# SPI_IFC.net
KiCad netlist of a schematic drawn in Altium Designer
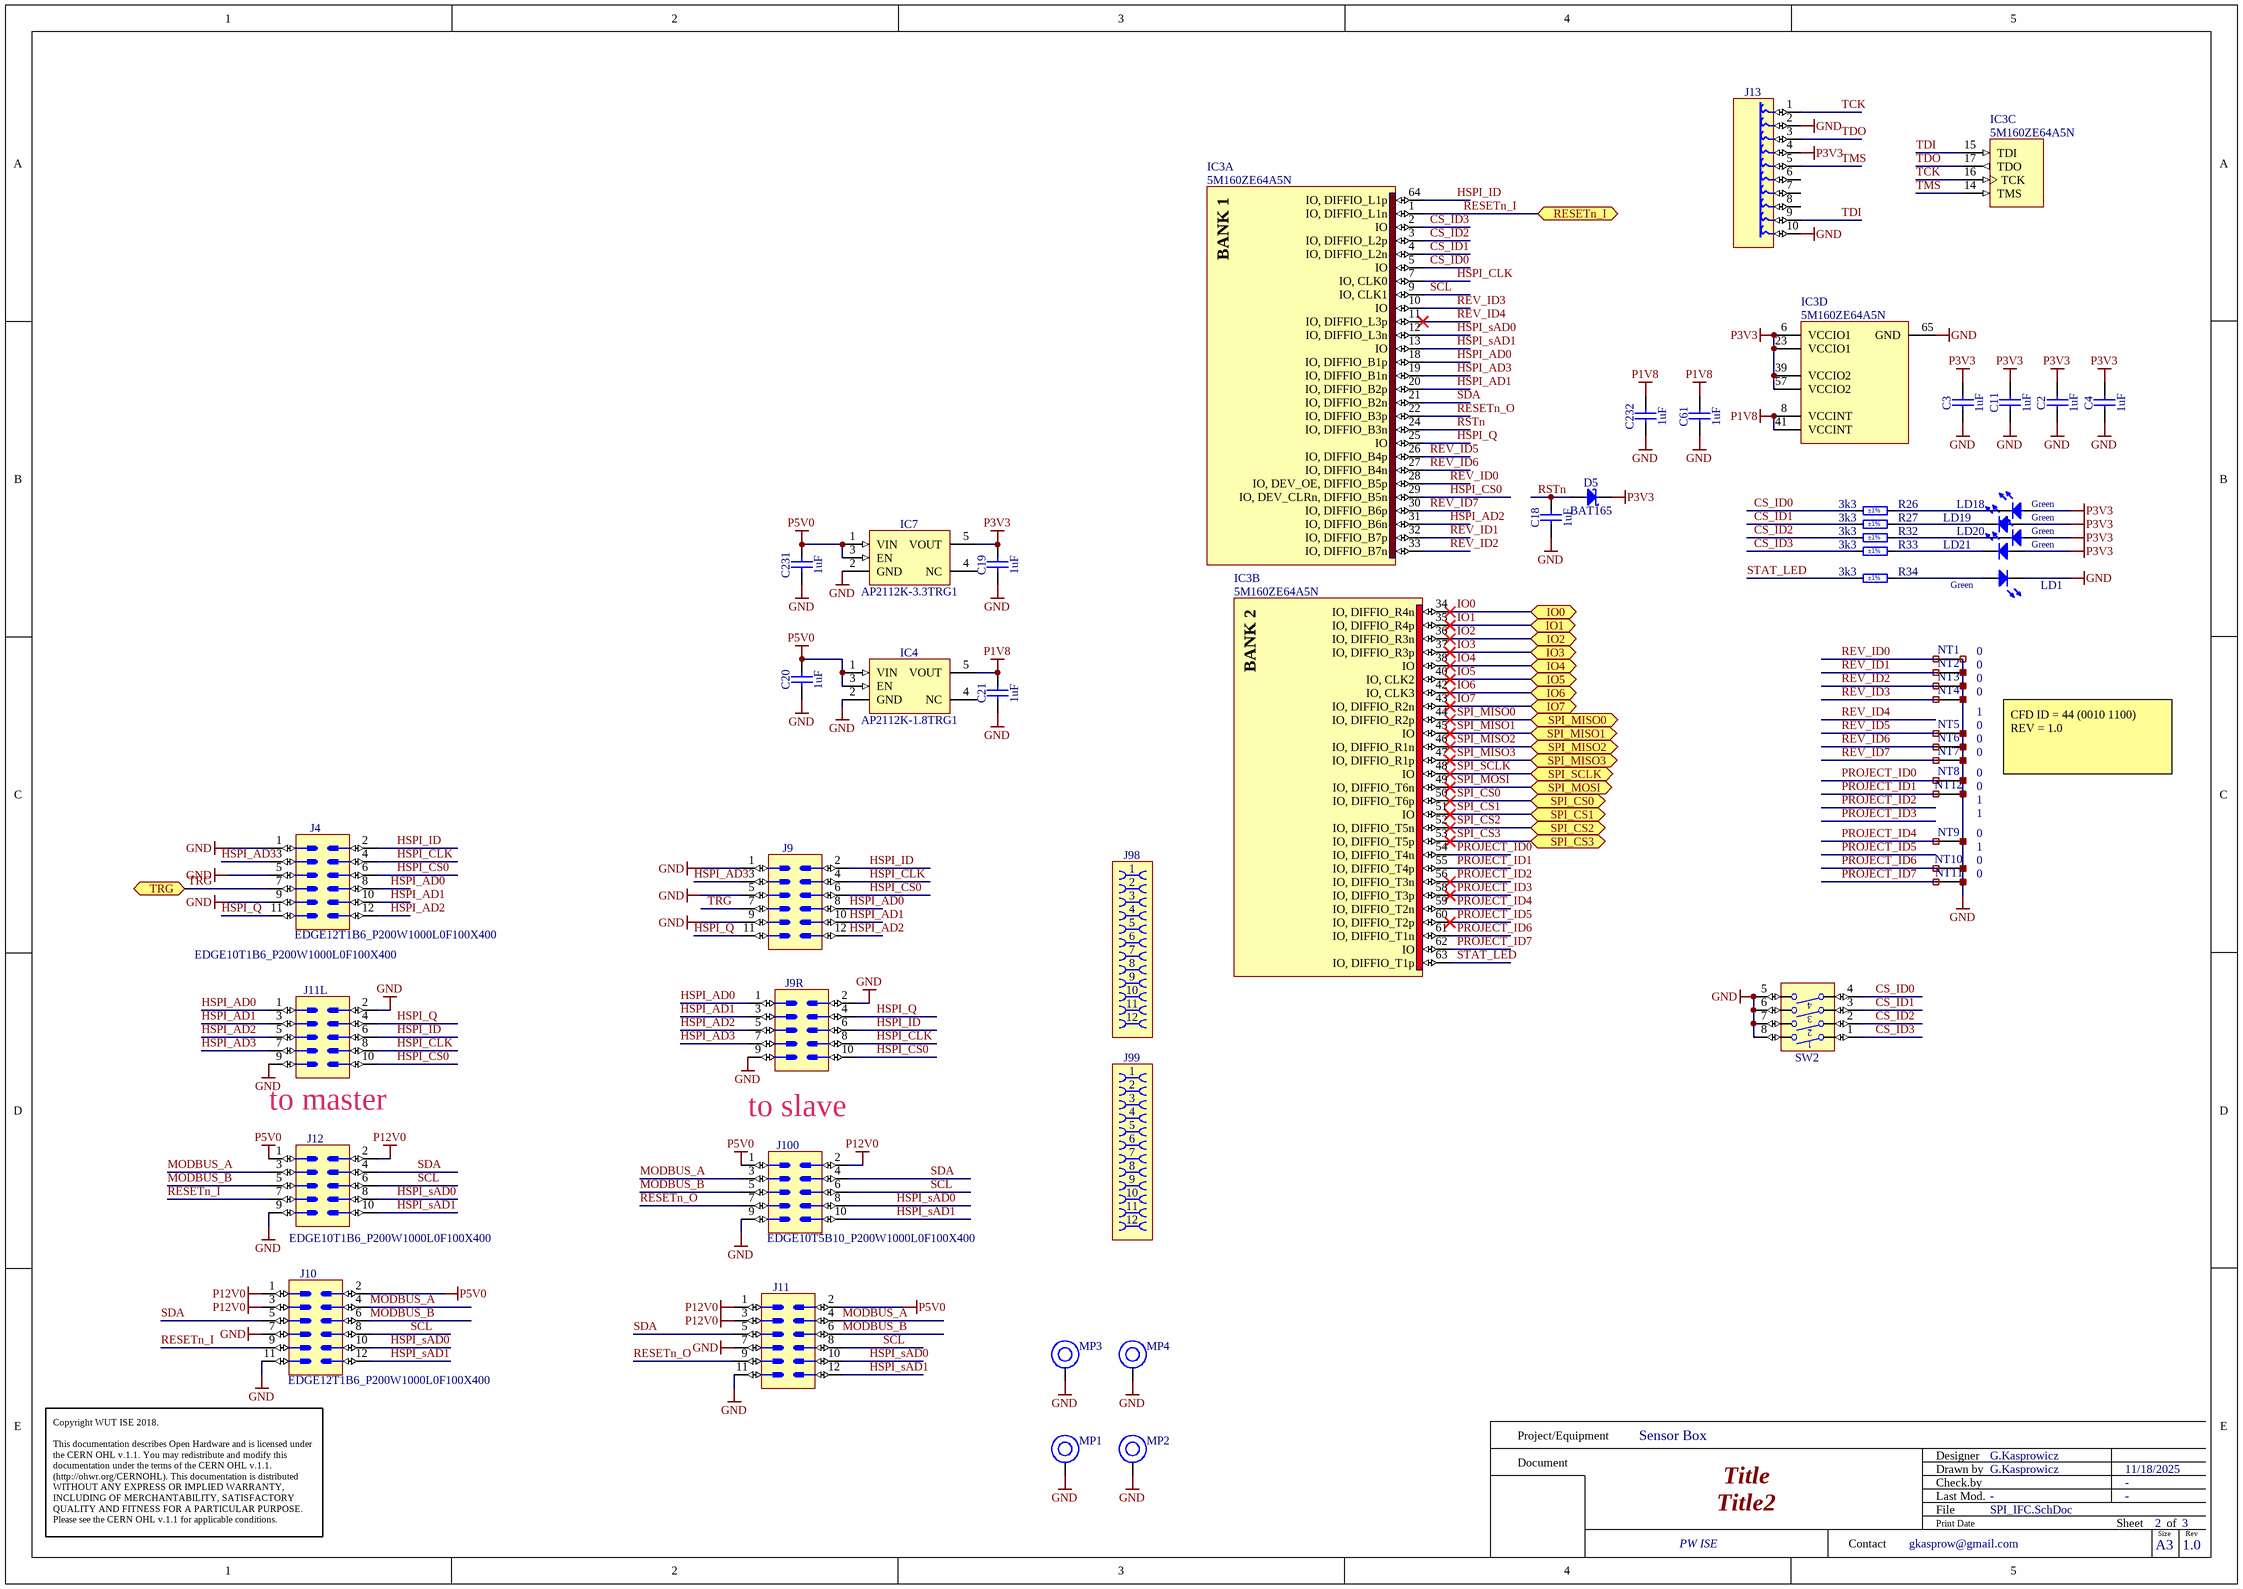
[diagram p0: SPI_IFC.SchDoc]

(export (version "E")
  (design (tool "Eeschema 10.0.6"))
  (components
    (comp (ref "C2")
      (value "1uF")
      (footprint "CAPC1005X55N")
      (description "Non-polarised capacitor")
      (fields
        (field (name "PART NUMBER") "CC0402_1UF_16V_10%_X5R")
        (field (name "VOLTAGE") "16V")
        (field (name "AUTHOR") "CERN DEM JLC")
      )
      (libsource (lib "Capacitors") (part "Capacitor - non polarized"))
    )
    (comp (ref "C3")
      (value "1uF")
      (footprint "CAPC1005X55N")
      (description "Non-polarised capacitor")
      (fields
        (field (name "PART NUMBER") "CC0402_1UF_16V_10%_X5R")
        (field (name "VOLTAGE") "16V")
        (field (name "AUTHOR") "CERN DEM JLC")
      )
      (libsource (lib "Capacitors") (part "Capacitor - non polarized"))
    )
    (comp (ref "C4")
      (value "1uF")
      (footprint "CAPC1005X55N")
      (description "Non-polarised capacitor")
      (fields
        (field (name "PART NUMBER") "CC0402_1UF_16V_10%_X5R")
        (field (name "VOLTAGE") "16V")
        (field (name "AUTHOR") "CERN DEM JLC")
      )
      (libsource (lib "Capacitors") (part "Capacitor - non polarized"))
    )
    (comp (ref "C11")
      (value "1uF")
      (footprint "CAPC1005X55N")
      (description "Non-polarised capacitor")
      (fields
        (field (name "PART NUMBER") "CC0402_1UF_16V_10%_X5R")
        (field (name "VOLTAGE") "16V")
        (field (name "AUTHOR") "CERN DEM JLC")
      )
      (libsource (lib "Capacitors") (part "Capacitor - non polarized"))
    )
    (comp (ref "C18")
      (value "1uF")
      (footprint "CAPC1005X55N")
      (description "Non-polarised capacitor")
      (fields
        (field (name "PART NUMBER") "CC0402_1UF_16V_10%_X5R")
        (field (name "VOLTAGE") "16V")
        (field (name "AUTHOR") "CERN DEM JLC")
      )
      (libsource (lib "Capacitors") (part "Capacitor - non polarized"))
    )
    (comp (ref "C19")
      (value "1uF")
      (footprint "CAPC1005X55N")
      (description "Non-polarised capacitor")
      (fields
        (field (name "PART NUMBER") "CC0402_1UF_16V_10%_X5R")
        (field (name "VOLTAGE") "16V")
        (field (name "AUTHOR") "CERN DEM JLC")
      )
      (libsource (lib "Capacitors") (part "Capacitor - non polarized"))
    )
    (comp (ref "C20")
      (value "1uF")
      (footprint "CAPC1005X55N")
      (description "Non-polarised capacitor")
      (fields
        (field (name "PART NUMBER") "CC0402_1UF_16V_10%_X5R")
        (field (name "VOLTAGE") "16V")
        (field (name "AUTHOR") "CERN DEM JLC")
      )
      (libsource (lib "Capacitors") (part "Capacitor - non polarized"))
    )
    (comp (ref "C21")
      (value "1uF")
      (footprint "CAPC1005X55N")
      (description "Non-polarised capacitor")
      (fields
        (field (name "PART NUMBER") "CC0402_1UF_16V_10%_X5R")
        (field (name "VOLTAGE") "16V")
        (field (name "AUTHOR") "CERN DEM JLC")
      )
      (libsource (lib "Capacitors") (part "Capacitor - non polarized"))
    )
    (comp (ref "C61")
      (value "1uF")
      (footprint "CAPC1005X55N")
      (description "Non-polarised capacitor")
      (fields
        (field (name "PART NUMBER") "CC0402_1UF_16V_10%_X5R")
        (field (name "VOLTAGE") "16V")
        (field (name "AUTHOR") "CERN DEM JLC")
      )
      (libsource (lib "Capacitors") (part "Capacitor - non polarized"))
    )
    (comp (ref "C231")
      (value "1uF")
      (footprint "CAPC1005X55N")
      (description "Non-polarised capacitor")
      (fields
        (field (name "PART NUMBER") "CC0402_1UF_16V_10%_X5R")
        (field (name "VOLTAGE") "16V")
        (field (name "AUTHOR") "CERN DEM JLC")
      )
      (libsource (lib "Capacitors") (part "Capacitor - non polarized"))
    )
    (comp (ref "C232")
      (value "1uF")
      (footprint "CAPC1005X55N")
      (description "Non-polarised capacitor")
      (fields
        (field (name "PART NUMBER") "CC0402_1UF_16V_10%_X5R")
        (field (name "VOLTAGE") "16V")
        (field (name "AUTHOR") "CERN DEM JLC")
      )
      (libsource (lib "Capacitors") (part "Capacitor - non polarized"))
    )
    (comp (ref "D5")
      (value "BAT165")
      (footprint "SOD2512X110N")
      (description "Schottky Diode")
      (fields
        (field (name "VOLTAGE") "40V")
        (field (name "POWER") "750mA")
        (field (name "AUTHOR") "CERN DEM JLC")
      )
      (libsource (lib "ICs And Semiconductors") (part "Diode Schottky"))
    )
    (comp (ref "IC3")
      (value "5M160ZE64A5N")
      (footprint "QFP40P900X900X120-65N-S550")
      (fields (field (name "MANUFACTURER") "ALTERA") (field (name "AUTHOR") "CERN DEM JLC"))
      (libsource (lib "ICs And Semiconductors") (part "5M160ZE64A5N"))
    )
    (comp (ref "IC4")
      (value "AP2112K-1.8TRG1")
      (footprint "SOT95P285X140-5N")
      (description "600mA CMOS Low Dropout Linear Regulator with Enable")
      (fields
        (field (name "MANUFACTURER") "DIODES INCORPORATED")
        (field (name "MANUFACTURER PART NUMBER") "AP2112K-1.8")
        (field (name "AUTHOR") "CERN DEM JLC")
      )
      (libsource (lib "ICs And Semiconductors") (part "AP2112K"))
    )
    (comp (ref "IC7")
      (value "AP2112K-3.3TRG1")
      (footprint "SOT95P285X140-5N")
      (description "600mA CMOS Low Dropout Linear Regulator with Enable")
      (fields
        (field (name "MANUFACTURER") "DIODES INCORPORATED")
        (field (name "MANUFACTURER PART NUMBER") "AP2112K-3.3")
        (field (name "AUTHOR") "CERN DEM MR")
      )
      (libsource (lib "ICs And Semiconductors") (part "AP2112K"))
    )
    (comp (ref "J4")
      (value "~")
      (footprint "EDGE12T1B6_P200W1000L0F100X400")
      (description "PCB Edge Connector 12 (2x6)")
      (fields
        (field (name "PART NUMBER") "EDGE10T1B6_P200W1000L0F100X400")
        (field (name "AUTHOR") "CERN DEM MR")
      )
      (libsource (lib "Connectors") (part "PCB Edge Connector 12 (2x6)"))
    )
    (comp (ref "J9")
      (value "~")
      (footprint "EDGE12T5B10_P200W1000L0F100X400")
      (description "PCB Edge Connector 12 (2x6)")
      (fields (field (name "PART NUMBER") "EDGE12T5B10_P200W1000L0F100X400") (field (name "AUTHOR") "GK"))
      (libsource (lib "Connectors") (part "PCB Edge Connector 12 (2x6) R"))
    )
    (comp (ref "J9R")
      (value "~")
      (footprint "EDGE10T5B10_P200W1000L0F100X400")
      (description "PCB Edge Connector 10 (2x5)")
      (fields
        (field (name "PART NUMBER") "EDGE10T5B10_P200W1000L0F100X400")
        (field (name "AUTHOR") "CERN DEM MR")
      )
      (libsource (lib "Connectors") (part "PCB Edge Connector 10 (2x5)"))
    )
    (comp (ref "J10")
      (value "~")
      (footprint "EDGE12T1B6_P200W1000L0F100X400")
      (description "PCB Edge Connector 12 (2x6)")
      (fields
        (field (name "PART NUMBER") "EDGE10T1B6_P200W1000L0F100X400")
        (field (name "AUTHOR") "CERN DEM MR")
      )
      (libsource (lib "Connectors") (part "PCB Edge Connector 12 (2x6)"))
    )
    (comp (ref "J11")
      (value "~")
      (footprint "EDGE12T5B10_P200W1000L0F100X400")
      (description "PCB Edge Connector 12 (2x6)")
      (fields (field (name "PART NUMBER") "EDGE12T5B10_P200W1000L0F100X400") (field (name "AUTHOR") "GK"))
      (libsource (lib "Connectors") (part "PCB Edge Connector 12 (2x6) R"))
    )
    (comp (ref "J11L")
      (value "~")
      (footprint "EDGE10T1B6_P200W1000L0F100X400")
      (description "PCB Edge Connector 10 (2x5)")
      (fields
        (field (name "PART NUMBER") "EDGE10T1B6_P200W1000L0F100X400")
        (field (name "AUTHOR") "CERN DEM MR")
      )
      (libsource (lib "Connectors") (part "PCB Edge Connector 10 (2x5)"))
    )
    (comp (ref "J12")
      (value "~")
      (footprint "EDGE10T1B6_P200W1000L0F100X400")
      (description "PCB Edge Connector 10 (2x5)")
      (fields
        (field (name "PART NUMBER") "EDGE10T1B6_P200W1000L0F100X400")
        (field (name "AUTHOR") "CERN DEM MR")
      )
      (libsource (lib "Connectors") (part "PCB Edge Connector 10 (2x5)"))
    )
    (comp (ref "J13")
      (value "TC2050-IDC")
      (footprint "TC2050-IDC")
      (description "TC2030-MCP and TC2050-IDC Pad Contact")
      (fields (field (name "AUTHOR") "CERN DEM HF"))
      (libsource (lib "Eletro-mechanical") (part "TC2050-IDC"))
    )
    (comp (ref "J98")
      (value "~")
      (footprint "AVX_009159012761916")
      (description "Open Ended Card Edge Connector, 9159 Series")
      (fields
        (field (name "PART NUMBER") "AVX_0009159012761916")
        (field (name "MANUFACTURER") "AVX")
        (field (name "AUTHOR") "GK")
      )
      (libsource (lib "Connectors") (part "AVX_009159012761916"))
    )
    (comp (ref "J99")
      (value "~")
      (footprint "AVX_009159012761916")
      (description "Open Ended Card Edge Connector, 9159 Series")
      (fields
        (field (name "PART NUMBER") "AVX_0009159012761916")
        (field (name "MANUFACTURER") "AVX")
        (field (name "AUTHOR") "GK")
      )
      (libsource (lib "Connectors") (part "AVX_009159012761916"))
    )
    (comp (ref "J100")
      (value "~")
      (footprint "EDGE10T5B10_P200W1000L0F100X400")
      (description "PCB Edge Connector 10 (2x5)")
      (fields
        (field (name "PART NUMBER") "EDGE10T5B10_P200W1000L0F100X400")
        (field (name "AUTHOR") "CERN DEM MR")
      )
      (libsource (lib "Connectors") (part "PCB Edge Connector 10 (2x5)"))
    )
    (comp (ref "LD1")
      (value "Green")
      (footprint "LED_KINGBRIGHT_KP-1608CGCK")
      (description "LED Green 1C 2A")
      (fields
        (field (name "PART NUMBER") "LED_KINGBRIGHT_KP-1608CGCK")
        (field (name "MANUFACTURER") "KINGBRIGHT")
        (field (name "AUTHOR") "CERN DEM HF")
      )
      (libsource (lib "ICs And Semiconductors") (part "LED Green 1C 2A"))
    )
    (comp (ref "LD18")
      (value "Green")
      (footprint "LED_KINGBRIGHT_KP-1608CGCK")
      (description "LED Green 1C 2A")
      (fields
        (field (name "PART NUMBER") "LED_KINGBRIGHT_KP-1608CGCK")
        (field (name "MANUFACTURER") "KINGBRIGHT")
        (field (name "AUTHOR") "CERN DEM HF")
      )
      (libsource (lib "ICs And Semiconductors") (part "LED Green 1C 2A"))
    )
    (comp (ref "LD19")
      (value "Green")
      (footprint "LED_KINGBRIGHT_KP-1608CGCK")
      (description "LED Green 1C 2A")
      (fields
        (field (name "PART NUMBER") "LED_KINGBRIGHT_KP-1608CGCK")
        (field (name "MANUFACTURER") "KINGBRIGHT")
        (field (name "AUTHOR") "CERN DEM HF")
      )
      (libsource (lib "ICs And Semiconductors") (part "LED Green 1C 2A"))
    )
    (comp (ref "LD20")
      (value "Green")
      (footprint "LED_KINGBRIGHT_KP-1608CGCK")
      (description "LED Green 1C 2A")
      (fields
        (field (name "PART NUMBER") "LED_KINGBRIGHT_KP-1608CGCK")
        (field (name "MANUFACTURER") "KINGBRIGHT")
        (field (name "AUTHOR") "CERN DEM HF")
      )
      (libsource (lib "ICs And Semiconductors") (part "LED Green 1C 2A"))
    )
    (comp (ref "LD21")
      (value "Green")
      (footprint "LED_KINGBRIGHT_KP-1608CGCK")
      (description "LED Green 1C 2A")
      (fields
        (field (name "PART NUMBER") "LED_KINGBRIGHT_KP-1608CGCK")
        (field (name "MANUFACTURER") "KINGBRIGHT")
        (field (name "AUTHOR") "CERN DEM HF")
      )
      (libsource (lib "ICs And Semiconductors") (part "LED Green 1C 2A"))
    )
    (comp (ref "MP1")
      (value "M1.6 x 3mm")
      (footprint "97730306330")
      (description "WA-SMSI SMT Steel Spacer with internal Thread Bottom closed, OD 3.3mm, M1.6 x 3mm")
      (fields
        (field (name "MANUFACTURER PART NUMBER") "97730306330R")
        (field (name "MANUFACTURER") "Wurth Elektronik")
      )
      (libsource (lib "Altium_WA-SMSI (rev22a)") (part "97730306330R"))
    )
    (comp (ref "MP2")
      (value "M1.6 x 3mm")
      (footprint "97730306330")
      (description "WA-SMSI SMT Steel Spacer with internal Thread Bottom closed, OD 3.3mm, M1.6 x 3mm")
      (fields
        (field (name "MANUFACTURER PART NUMBER") "97730306330R")
        (field (name "MANUFACTURER") "Wurth Elektronik")
      )
      (libsource (lib "Altium_WA-SMSI (rev22a)") (part "97730306330R"))
    )
    (comp (ref "MP3")
      (value "M1.6 x 3mm")
      (footprint "97730306330")
      (description "WA-SMSI SMT Steel Spacer with internal Thread Bottom closed, OD 3.3mm, M1.6 x 3mm")
      (fields
        (field (name "MANUFACTURER PART NUMBER") "97730306330R")
        (field (name "MANUFACTURER") "Wurth Elektronik")
      )
      (libsource (lib "Altium_WA-SMSI (rev22a)") (part "97730306330R"))
    )
    (comp (ref "MP4")
      (value "M1.6 x 3mm")
      (footprint "97730306330")
      (description "WA-SMSI SMT Steel Spacer with internal Thread Bottom closed, OD 3.3mm, M1.6 x 3mm")
      (fields
        (field (name "MANUFACTURER PART NUMBER") "97730306330R")
        (field (name "MANUFACTURER") "Wurth Elektronik")
      )
      (libsource (lib "Altium_WA-SMSI (rev22a)") (part "97730306330R"))
    )
    (comp (ref "NT1")
      (value "Net Tie")
      (footprint "Net Tie 3")
      (fields (field (name "PART NUMBER") "Net Tie 3") (field (name "AUTHOR") "CERN DEM HF"))
      (libsource (lib "Eletro-mechanical") (part "Net Tie_a"))
    )
    (comp (ref "NT2")
      (value "Net Tie")
      (footprint "Net Tie 3")
      (fields (field (name "PART NUMBER") "Net Tie 3") (field (name "AUTHOR") "CERN DEM HF"))
      (libsource (lib "Eletro-mechanical") (part "Net Tie_a"))
    )
    (comp (ref "NT3")
      (value "Net Tie")
      (footprint "Net Tie 3")
      (fields (field (name "PART NUMBER") "Net Tie 3") (field (name "AUTHOR") "CERN DEM HF"))
      (libsource (lib "Eletro-mechanical") (part "Net Tie_a"))
    )
    (comp (ref "NT4")
      (value "Net Tie")
      (footprint "Net Tie 3")
      (fields (field (name "PART NUMBER") "Net Tie 3") (field (name "AUTHOR") "CERN DEM HF"))
      (libsource (lib "Eletro-mechanical") (part "Net Tie_a"))
    )
    (comp (ref "NT5")
      (value "Net Tie")
      (footprint "Net Tie 3")
      (fields (field (name "PART NUMBER") "Net Tie 3") (field (name "AUTHOR") "CERN DEM HF"))
      (libsource (lib "Eletro-mechanical") (part "Net Tie_a"))
    )
    (comp (ref "NT6")
      (value "Net Tie")
      (footprint "Net Tie 3")
      (fields (field (name "PART NUMBER") "Net Tie 3") (field (name "AUTHOR") "CERN DEM HF"))
      (libsource (lib "Eletro-mechanical") (part "Net Tie_a"))
    )
    (comp (ref "NT7")
      (value "Net Tie")
      (footprint "Net Tie 3")
      (fields (field (name "PART NUMBER") "Net Tie 3") (field (name "AUTHOR") "CERN DEM HF"))
      (libsource (lib "Eletro-mechanical") (part "Net Tie_a"))
    )
    (comp (ref "NT8")
      (value "Net Tie")
      (footprint "Net Tie 3")
      (fields (field (name "PART NUMBER") "Net Tie 3") (field (name "AUTHOR") "CERN DEM HF"))
      (libsource (lib "Eletro-mechanical") (part "Net Tie_a"))
    )
    (comp (ref "NT9")
      (value "Net Tie")
      (footprint "Net Tie 3")
      (fields (field (name "PART NUMBER") "Net Tie 3") (field (name "AUTHOR") "CERN DEM HF"))
      (libsource (lib "Eletro-mechanical") (part "Net Tie_a"))
    )
    (comp (ref "NT10")
      (value "Net Tie")
      (footprint "Net Tie 3")
      (fields (field (name "PART NUMBER") "Net Tie 3") (field (name "AUTHOR") "CERN DEM HF"))
      (libsource (lib "Eletro-mechanical") (part "Net Tie_a"))
    )
    (comp (ref "NT11")
      (value "Net Tie")
      (footprint "Net Tie 3")
      (fields (field (name "PART NUMBER") "Net Tie 3") (field (name "AUTHOR") "CERN DEM HF"))
      (libsource (lib "Eletro-mechanical") (part "Net Tie_a"))
    )
    (comp (ref "NT12")
      (value "Net Tie")
      (footprint "Net Tie 3")
      (fields (field (name "PART NUMBER") "Net Tie 3") (field (name "AUTHOR") "CERN DEM HF"))
      (libsource (lib "Eletro-mechanical") (part "Net Tie_a"))
    )
    (comp (ref "R26")
      (value "3k3")
      (footprint "RESC1005X40N")
      (description "Resistor - 1%")
      (fields
        (field (name "TOLERANCE") "±1%")
        (field (name "PART NUMBER") "R0402_3K3_1%_0.0625W_100PPM")
        (field (name "POWER") "0.0625W")
        (field (name "AUTHOR") "CERN DEM JLC")
      )
      (libsource (lib "Resistors") (part "Resistor - 1%"))
    )
    (comp (ref "R27")
      (value "3k3")
      (footprint "RESC1005X40N")
      (description "Resistor - 1%")
      (fields
        (field (name "TOLERANCE") "±1%")
        (field (name "PART NUMBER") "R0402_3K3_1%_0.0625W_100PPM")
        (field (name "POWER") "0.0625W")
        (field (name "AUTHOR") "CERN DEM JLC")
      )
      (libsource (lib "Resistors") (part "Resistor - 1%"))
    )
    (comp (ref "R32")
      (value "3k3")
      (footprint "RESC1005X40N")
      (description "Resistor - 1%")
      (fields
        (field (name "TOLERANCE") "±1%")
        (field (name "PART NUMBER") "R0402_3K3_1%_0.0625W_100PPM")
        (field (name "POWER") "0.0625W")
        (field (name "AUTHOR") "CERN DEM JLC")
      )
      (libsource (lib "Resistors") (part "Resistor - 1%"))
    )
    (comp (ref "R33")
      (value "3k3")
      (footprint "RESC1005X40N")
      (description "Resistor - 1%")
      (fields
        (field (name "TOLERANCE") "±1%")
        (field (name "PART NUMBER") "R0402_3K3_1%_0.0625W_100PPM")
        (field (name "POWER") "0.0625W")
        (field (name "AUTHOR") "CERN DEM JLC")
      )
      (libsource (lib "Resistors") (part "Resistor - 1%"))
    )
    (comp (ref "R34")
      (value "3k3")
      (footprint "RESC1005X40N")
      (description "Resistor - 1%")
      (fields
        (field (name "TOLERANCE") "±1%")
        (field (name "PART NUMBER") "R0402_3K3_1%_0.0625W_100PPM")
        (field (name "POWER") "0.0625W")
        (field (name "AUTHOR") "CERN DEM JLC")
      )
      (libsource (lib "Resistors") (part "Resistor - 1%"))
    )
    (comp (ref "SW2")
      (value "Switch")
      (footprint "SW_OMRON_A6H-4102")
      (description "4 Ways SPST DIP Switch")
      (fields
        (field (name "PART NUMBER") "SW_OMRON_A6H-4102")
        (field (name "MANUFACTURER") "OMRON")
        (field (name "AUTHOR") "CERN DEM JLC")
      )
      (libsource (lib "Eletro-mechanical") (part "SW 4x SPST DIP Switch"))
    )
  )
  (nets
    (net (code "1") (name "/CS_ID0") (class "Default")
      (node (ref "IC3") (pin "5") (pinfunction "IO_5") (pintype "bidirectional"))
      (node (ref "R26") (pin "2") (pinfunction "2_2") (pintype "passive"))
      (node (ref "SW2") (pin "4") (pinfunction "4_4") (pintype "bidirectional"))
    )
    (net (code "2") (name "/CS_ID1") (class "Default")
      (node (ref "IC3") (pin "4") (pinfunction "IO,_DIFFIO_L2n_4") (pintype "bidirectional"))
      (node (ref "R27") (pin "2") (pinfunction "2_2") (pintype "passive"))
      (node (ref "SW2") (pin "3") (pinfunction "3_3") (pintype "bidirectional"))
    )
    (net (code "3") (name "/CS_ID2") (class "Default")
      (node (ref "IC3") (pin "3") (pinfunction "IO,_DIFFIO_L2p_3") (pintype "bidirectional"))
      (node (ref "R32") (pin "2") (pinfunction "2_2") (pintype "passive"))
      (node (ref "SW2") (pin "2") (pinfunction "2_2") (pintype "bidirectional"))
    )
    (net (code "4") (name "/CS_ID3") (class "Default")
      (node (ref "IC3") (pin "2") (pinfunction "IO_2") (pintype "bidirectional"))
      (node (ref "R33") (pin "2") (pinfunction "2_2") (pintype "passive"))
      (node (ref "SW2") (pin "1") (pinfunction "1_1") (pintype "bidirectional"))
    )
    (net (code "5") (name "/HSPI_AD0") (class "Default")
      (node (ref "IC3") (pin "18") (pinfunction "IO,_DIFFIO_B1p_18") (pintype "bidirectional"))
      (node (ref "J11L") (pin "1") (pinfunction "1_1") (pintype "bidirectional"))
      (node (ref "J4") (pin "8") (pinfunction "8_8") (pintype "bidirectional"))
      (node (ref "J9") (pin "8") (pinfunction "8_8") (pintype "bidirectional"))
      (node (ref "J9R") (pin "1") (pinfunction "1_1") (pintype "bidirectional"))
    )
    (net (code "6") (name "/HSPI_AD1") (class "Default")
      (node (ref "IC3") (pin "20") (pinfunction "IO,_DIFFIO_B2p_20") (pintype "bidirectional"))
      (node (ref "J11L") (pin "3") (pinfunction "3_3") (pintype "bidirectional"))
      (node (ref "J4") (pin "10") (pinfunction "10_10") (pintype "bidirectional"))
      (node (ref "J9") (pin "10") (pinfunction "10_10") (pintype "bidirectional"))
      (node (ref "J9R") (pin "3") (pinfunction "3_3") (pintype "bidirectional"))
    )
    (net (code "7") (name "/HSPI_AD2") (class "Default")
      (node (ref "IC3") (pin "31") (pinfunction "IO,_DIFFIO_B6n_31") (pintype "bidirectional"))
      (node (ref "J11L") (pin "5") (pinfunction "5_5") (pintype "bidirectional"))
      (node (ref "J4") (pin "12") (pinfunction "12_12") (pintype "bidirectional"))
      (node (ref "J9") (pin "12") (pinfunction "12_12") (pintype "bidirectional"))
      (node (ref "J9R") (pin "5") (pinfunction "5_5") (pintype "bidirectional"))
    )
    (net (code "8") (name "/HSPI_AD3") (class "Default")
      (node (ref "IC3") (pin "19") (pinfunction "IO,_DIFFIO_B1n_19") (pintype "bidirectional"))
      (node (ref "J11L") (pin "7") (pinfunction "7_7") (pintype "bidirectional"))
      (node (ref "J4") (pin "3") (pinfunction "3_3") (pintype "bidirectional"))
      (node (ref "J9") (pin "3") (pinfunction "3_3") (pintype "bidirectional"))
      (node (ref "J9R") (pin "7") (pinfunction "7_7") (pintype "bidirectional"))
    )
    (net (code "9") (name "/HSPI_CLK") (class "Default")
      (node (ref "IC3") (pin "7") (pinfunction "IO,_CLK0_7") (pintype "bidirectional"))
      (node (ref "J11L") (pin "8") (pinfunction "8_8") (pintype "bidirectional"))
      (node (ref "J4") (pin "4") (pinfunction "4_4") (pintype "bidirectional"))
      (node (ref "J9") (pin "4") (pinfunction "4_4") (pintype "bidirectional"))
      (node (ref "J9R") (pin "8") (pinfunction "8_8") (pintype "bidirectional"))
    )
    (net (code "10") (name "/HSPI_CS0") (class "Default")
      (node (ref "IC3") (pin "29") (pinfunction "IO,_DEV_CLRn,_DIFFIO_B5n_29") (pintype "bidirectional"))
      (node (ref "J11L") (pin "10") (pinfunction "10_10") (pintype "bidirectional"))
      (node (ref "J4") (pin "6") (pinfunction "6_6") (pintype "bidirectional"))
      (node (ref "J9") (pin "6") (pinfunction "6_6") (pintype "bidirectional"))
      (node (ref "J9R") (pin "10") (pinfunction "10_10") (pintype "bidirectional"))
    )
    (net (code "11") (name "/HSPI_ID") (class "Default")
      (node (ref "IC3") (pin "64") (pinfunction "IO,_DIFFIO_L1p_64") (pintype "bidirectional"))
      (node (ref "J11L") (pin "6") (pinfunction "6_6") (pintype "bidirectional"))
      (node (ref "J4") (pin "2") (pinfunction "2_2") (pintype "bidirectional"))
      (node (ref "J9") (pin "2") (pinfunction "2_2") (pintype "bidirectional"))
      (node (ref "J9R") (pin "6") (pinfunction "6_6") (pintype "bidirectional"))
    )
    (net (code "12") (name "/HSPI_Q") (class "Default")
      (node (ref "IC3") (pin "25") (pinfunction "IO_25") (pintype "bidirectional"))
      (node (ref "J11L") (pin "4") (pinfunction "4_4") (pintype "bidirectional"))
      (node (ref "J4") (pin "11") (pinfunction "11_11") (pintype "bidirectional"))
      (node (ref "J9") (pin "11") (pinfunction "11_11") (pintype "bidirectional"))
      (node (ref "J9R") (pin "4") (pinfunction "4_4") (pintype "bidirectional"))
    )
    (net (code "13") (name "/HSPI_sAD0") (class "Default")
      (node (ref "IC3") (pin "12") (pinfunction "IO,_DIFFIO_L3n_12") (pintype "bidirectional"))
      (node (ref "J10") (pin "10") (pinfunction "10_10") (pintype "bidirectional"))
      (node (ref "J100") (pin "8") (pinfunction "8_8") (pintype "bidirectional"))
      (node (ref "J11") (pin "10") (pinfunction "10_10") (pintype "bidirectional"))
      (node (ref "J12") (pin "8") (pinfunction "8_8") (pintype "bidirectional"))
    )
    (net (code "14") (name "/HSPI_sAD1") (class "Default")
      (node (ref "IC3") (pin "13") (pinfunction "IO_13") (pintype "bidirectional"))
      (node (ref "J10") (pin "12") (pinfunction "12_12") (pintype "bidirectional"))
      (node (ref "J100") (pin "10") (pinfunction "10_10") (pintype "bidirectional"))
      (node (ref "J11") (pin "12") (pinfunction "12_12") (pintype "bidirectional"))
      (node (ref "J12") (pin "10") (pinfunction "10_10") (pintype "bidirectional"))
    )
    (net (code "15") (name "/IO0") (class "Default")
      (node (ref "IC3") (pin "34") (pinfunction "IO,_DIFFIO_R4n_34") (pintype "bidirectional+no_connect"))
    )
    (net (code "16") (name "/IO1") (class "Default")
      (node (ref "IC3") (pin "35") (pinfunction "IO,_DIFFIO_R4p_35") (pintype "bidirectional+no_connect"))
    )
    (net (code "17") (name "/IO2") (class "Default")
      (node (ref "IC3") (pin "36") (pinfunction "IO,_DIFFIO_R3n_36") (pintype "bidirectional+no_connect"))
    )
    (net (code "18") (name "/IO3") (class "Default")
      (node (ref "IC3") (pin "37") (pinfunction "IO,_DIFFIO_R3p_37") (pintype "bidirectional+no_connect"))
    )
    (net (code "19") (name "/IO4") (class "Default")
      (node (ref "IC3") (pin "38") (pinfunction "IO_38") (pintype "bidirectional+no_connect"))
    )
    (net (code "20") (name "/IO5") (class "Default")
      (node (ref "IC3") (pin "40") (pinfunction "IO,_CLK2_40") (pintype "bidirectional+no_connect"))
    )
    (net (code "21") (name "/IO6") (class "Default")
      (node (ref "IC3") (pin "42") (pinfunction "IO,_CLK3_42") (pintype "bidirectional+no_connect"))
    )
    (net (code "22") (name "/IO7") (class "Default")
      (node (ref "IC3") (pin "43") (pinfunction "IO,_DIFFIO_R2n_43") (pintype "bidirectional+no_connect"))
    )
    (net (code "23") (name "/MODBUS_A") (class "Default")
      (node (ref "J10") (pin "4") (pinfunction "4_4") (pintype "bidirectional"))
      (node (ref "J100") (pin "3") (pinfunction "3_3") (pintype "bidirectional"))
      (node (ref "J11") (pin "4") (pinfunction "4_4") (pintype "bidirectional"))
      (node (ref "J12") (pin "3") (pinfunction "3_3") (pintype "bidirectional"))
    )
    (net (code "24") (name "/MODBUS_B") (class "Default")
      (node (ref "J10") (pin "6") (pinfunction "6_6") (pintype "bidirectional"))
      (node (ref "J100") (pin "5") (pinfunction "5_5") (pintype "bidirectional"))
      (node (ref "J11") (pin "6") (pinfunction "6_6") (pintype "bidirectional"))
      (node (ref "J12") (pin "5") (pinfunction "5_5") (pintype "bidirectional"))
    )
    (net (code "25") (name "/PROJECT_ID0") (class "Default")
      (node (ref "IC3") (pin "54") (pinfunction "IO,_DIFFIO_T4n_54") (pintype "bidirectional"))
      (node (ref "NT8") (pin "1") (pinfunction "1_1") (pintype "bidirectional"))
    )
    (net (code "26") (name "/PROJECT_ID1") (class "Default")
      (node (ref "IC3") (pin "55") (pinfunction "IO,_DIFFIO_T4p_55") (pintype "bidirectional"))
      (node (ref "NT12") (pin "1") (pinfunction "1_1") (pintype "bidirectional"))
    )
    (net (code "27") (name "/PROJECT_ID2") (class "Default")
      (node (ref "IC3") (pin "56") (pinfunction "IO,_DIFFIO_T3n_56") (pintype "bidirectional+no_connect"))
    )
    (net (code "28") (name "/PROJECT_ID3") (class "Default")
      (node (ref "IC3") (pin "58") (pinfunction "IO,_DIFFIO_T3p_58") (pintype "bidirectional+no_connect"))
    )
    (net (code "29") (name "/PROJECT_ID4") (class "Default")
      (node (ref "IC3") (pin "59") (pinfunction "IO,_DIFFIO_T2n_59") (pintype "bidirectional"))
      (node (ref "NT9") (pin "1") (pinfunction "1_1") (pintype "bidirectional"))
    )
    (net (code "30") (name "/PROJECT_ID5") (class "Default")
      (node (ref "IC3") (pin "60") (pinfunction "IO,_DIFFIO_T2p_60") (pintype "bidirectional+no_connect"))
    )
    (net (code "31") (name "/PROJECT_ID6") (class "Default")
      (node (ref "IC3") (pin "61") (pinfunction "IO,_DIFFIO_T1n_61") (pintype "bidirectional"))
      (node (ref "NT10") (pin "1") (pinfunction "1_1") (pintype "bidirectional"))
    )
    (net (code "32") (name "/PROJECT_ID7") (class "Default")
      (node (ref "IC3") (pin "62") (pinfunction "IO_62") (pintype "bidirectional"))
      (node (ref "NT11") (pin "1") (pinfunction "1_1") (pintype "bidirectional"))
    )
    (net (code "33") (name "/RESETn_I") (class "Default")
      (node (ref "IC3") (pin "1") (pinfunction "IO,_DIFFIO_L1n_1") (pintype "bidirectional"))
      (node (ref "J10") (pin "9") (pinfunction "9_9") (pintype "bidirectional"))
      (node (ref "J12") (pin "7") (pinfunction "7_7") (pintype "bidirectional"))
    )
    (net (code "34") (name "/RESETn_O") (class "Default")
      (node (ref "IC3") (pin "22") (pinfunction "IO,_DIFFIO_B3p_22") (pintype "bidirectional"))
      (node (ref "J100") (pin "7") (pinfunction "7_7") (pintype "bidirectional"))
      (node (ref "J11") (pin "9") (pinfunction "9_9") (pintype "bidirectional"))
    )
    (net (code "35") (name "/REV_ID0") (class "Default")
      (node (ref "IC3") (pin "28") (pinfunction "IO,_DEV_OE,_DIFFIO_B5p_28") (pintype "bidirectional"))
      (node (ref "NT1") (pin "1") (pinfunction "1_1") (pintype "bidirectional"))
    )
    (net (code "36") (name "/REV_ID1") (class "Default")
      (node (ref "IC3") (pin "32") (pinfunction "IO,_DIFFIO_B7p_32") (pintype "bidirectional"))
      (node (ref "NT2") (pin "1") (pinfunction "1_1") (pintype "bidirectional"))
    )
    (net (code "37") (name "/REV_ID2") (class "Default")
      (node (ref "IC3") (pin "33") (pinfunction "IO,_DIFFIO_B7n_33") (pintype "bidirectional"))
      (node (ref "NT3") (pin "1") (pinfunction "1_1") (pintype "bidirectional"))
    )
    (net (code "38") (name "/REV_ID3") (class "Default")
      (node (ref "IC3") (pin "10") (pinfunction "IO_10") (pintype "bidirectional"))
      (node (ref "NT4") (pin "1") (pinfunction "1_1") (pintype "bidirectional"))
    )
    (net (code "39") (name "/REV_ID4") (class "Default")
      (node (ref "IC3") (pin "11") (pinfunction "IO,_DIFFIO_L3p_11") (pintype "bidirectional+no_connect"))
    )
    (net (code "40") (name "/REV_ID5") (class "Default")
      (node (ref "IC3") (pin "26") (pinfunction "IO,_DIFFIO_B4p_26") (pintype "bidirectional"))
      (node (ref "NT5") (pin "1") (pinfunction "1_1") (pintype "bidirectional"))
    )
    (net (code "41") (name "/REV_ID6") (class "Default")
      (node (ref "IC3") (pin "27") (pinfunction "IO,_DIFFIO_B4n_27") (pintype "bidirectional"))
      (node (ref "NT6") (pin "1") (pinfunction "1_1") (pintype "bidirectional"))
    )
    (net (code "42") (name "/REV_ID7") (class "Default")
      (node (ref "IC3") (pin "30") (pinfunction "IO,_DIFFIO_B6p_30") (pintype "bidirectional"))
      (node (ref "NT7") (pin "1") (pinfunction "1_1") (pintype "bidirectional"))
    )
    (net (code "43") (name "/RSTn") (class "Default")
      (node (ref "C18") (pin "2") (pinfunction "2_2") (pintype "passive"))
      (node (ref "D5") (pin "2") (pinfunction "A_2") (pintype "passive"))
      (node (ref "IC3") (pin "24") (pinfunction "IO,_DIFFIO_B3n_24") (pintype "bidirectional"))
    )
    (net (code "44") (name "/SCL") (class "Default")
      (node (ref "IC3") (pin "9") (pinfunction "IO,_CLK1_9") (pintype "bidirectional"))
      (node (ref "J10") (pin "8") (pinfunction "8_8") (pintype "bidirectional"))
      (node (ref "J100") (pin "6") (pinfunction "6_6") (pintype "bidirectional"))
      (node (ref "J11") (pin "8") (pinfunction "8_8") (pintype "bidirectional"))
      (node (ref "J12") (pin "6") (pinfunction "6_6") (pintype "bidirectional"))
    )
    (net (code "45") (name "/SDA") (class "Default")
      (node (ref "IC3") (pin "21") (pinfunction "IO,_DIFFIO_B2n_21") (pintype "bidirectional"))
      (node (ref "J10") (pin "5") (pinfunction "5_5") (pintype "bidirectional"))
      (node (ref "J100") (pin "4") (pinfunction "4_4") (pintype "bidirectional"))
      (node (ref "J11") (pin "5") (pinfunction "5_5") (pintype "bidirectional"))
      (node (ref "J12") (pin "4") (pinfunction "4_4") (pintype "bidirectional"))
    )
    (net (code "46") (name "/SPI_CS0") (class "Default")
      (node (ref "IC3") (pin "50") (pinfunction "IO,_DIFFIO_T6p_50") (pintype "bidirectional+no_connect"))
    )
    (net (code "47") (name "/SPI_CS1") (class "Default")
      (node (ref "IC3") (pin "51") (pinfunction "IO_51") (pintype "bidirectional+no_connect"))
    )
    (net (code "48") (name "/SPI_CS2") (class "Default")
      (node (ref "IC3") (pin "52") (pinfunction "IO,_DIFFIO_T5n_52") (pintype "bidirectional+no_connect"))
    )
    (net (code "49") (name "/SPI_CS3") (class "Default")
      (node (ref "IC3") (pin "53") (pinfunction "IO,_DIFFIO_T5p_53") (pintype "bidirectional+no_connect"))
    )
    (net (code "50") (name "/SPI_MISO0") (class "Default")
      (node (ref "IC3") (pin "44") (pinfunction "IO,_DIFFIO_R2p_44") (pintype "bidirectional+no_connect"))
    )
    (net (code "51") (name "/SPI_MISO1") (class "Default")
      (node (ref "IC3") (pin "45") (pinfunction "IO_45") (pintype "bidirectional+no_connect"))
    )
    (net (code "52") (name "/SPI_MISO2") (class "Default")
      (node (ref "IC3") (pin "46") (pinfunction "IO,_DIFFIO_R1n_46") (pintype "bidirectional+no_connect"))
    )
    (net (code "53") (name "/SPI_MISO3") (class "Default")
      (node (ref "IC3") (pin "47") (pinfunction "IO,_DIFFIO_R1p_47") (pintype "bidirectional+no_connect"))
    )
    (net (code "54") (name "/SPI_MOSI") (class "Default")
      (node (ref "IC3") (pin "49") (pinfunction "IO,_DIFFIO_T6n_49") (pintype "bidirectional+no_connect"))
    )
    (net (code "55") (name "/SPI_SCLK") (class "Default")
      (node (ref "IC3") (pin "48") (pinfunction "IO_48") (pintype "bidirectional+no_connect"))
    )
    (net (code "56") (name "/STAT_LED") (class "Default")
      (node (ref "IC3") (pin "63") (pinfunction "IO,_DIFFIO_T1p_63") (pintype "bidirectional"))
      (node (ref "R34") (pin "2") (pinfunction "2_2") (pintype "passive"))
    )
    (net (code "57") (name "/TCK") (class "Default")
      (node (ref "IC3") (pin "16") (pinfunction "TCK_16") (pintype "input"))
      (node (ref "J13") (pin "1") (pinfunction "1_1") (pintype "bidirectional"))
    )
    (net (code "58") (name "/TDI") (class "Default")
      (node (ref "IC3") (pin "15") (pinfunction "TDI_15") (pintype "input"))
      (node (ref "J13") (pin "9") (pinfunction "9_9") (pintype "bidirectional"))
    )
    (net (code "59") (name "/TDO") (class "Default")
      (node (ref "IC3") (pin "17") (pinfunction "TDO_17") (pintype "output"))
      (node (ref "J13") (pin "3") (pinfunction "3_3") (pintype "bidirectional"))
    )
    (net (code "60") (name "/TMS") (class "Default")
      (node (ref "IC3") (pin "14") (pinfunction "TMS_14") (pintype "input"))
      (node (ref "J13") (pin "5") (pinfunction "5_5") (pintype "bidirectional"))
    )
    (net (code "61") (name "/TRG") (class "Default")
      (node (ref "J4") (pin "7") (pinfunction "7_7") (pintype "bidirectional"))
      (node (ref "J9") (pin "7") (pinfunction "7_7") (pintype "bidirectional"))
    )
    (net (code "62") (name "GND") (class "Default")
      (node (ref "C11") (pin "1") (pinfunction "1_1") (pintype "passive"))
      (node (ref "C18") (pin "1") (pinfunction "1_1") (pintype "passive"))
      (node (ref "C19") (pin "1") (pinfunction "1_1") (pintype "passive"))
      (node (ref "C2") (pin "1") (pinfunction "1_1") (pintype "passive"))
      (node (ref "C20") (pin "1") (pinfunction "1_1") (pintype "passive"))
      (node (ref "C21") (pin "1") (pinfunction "1_1") (pintype "passive"))
      (node (ref "C231") (pin "1") (pinfunction "1_1") (pintype "passive"))
      (node (ref "C232") (pin "1") (pinfunction "1_1") (pintype "passive"))
      (node (ref "C3") (pin "1") (pinfunction "1_1") (pintype "passive"))
      (node (ref "C4") (pin "1") (pinfunction "1_1") (pintype "passive"))
      (node (ref "C61") (pin "1") (pinfunction "1_1") (pintype "passive"))
      (node (ref "IC3") (pin "65") (pinfunction "GND_65") (pintype "power_in"))
      (node (ref "IC4") (pin "2") (pinfunction "GND_2") (pintype "power_in"))
      (node (ref "IC7") (pin "2") (pinfunction "GND_2") (pintype "power_in"))
      (node (ref "J10") (pin "11") (pinfunction "11_11") (pintype "bidirectional"))
      (node (ref "J10") (pin "7") (pinfunction "7_7") (pintype "bidirectional"))
      (node (ref "J100") (pin "9") (pinfunction "9_9") (pintype "bidirectional"))
      (node (ref "J11") (pin "11") (pinfunction "11_11") (pintype "bidirectional"))
      (node (ref "J11") (pin "7") (pinfunction "7_7") (pintype "bidirectional"))
      (node (ref "J11L") (pin "2") (pinfunction "2_2") (pintype "bidirectional"))
      (node (ref "J11L") (pin "9") (pinfunction "9_9") (pintype "bidirectional"))
      (node (ref "J12") (pin "9") (pinfunction "9_9") (pintype "bidirectional"))
      (node (ref "J13") (pin "10") (pinfunction "10_10") (pintype "bidirectional"))
      (node (ref "J13") (pin "2") (pinfunction "2_2") (pintype "bidirectional"))
      (node (ref "J4") (pin "1") (pinfunction "1_1") (pintype "bidirectional"))
      (node (ref "J4") (pin "5") (pinfunction "5_5") (pintype "bidirectional"))
      (node (ref "J4") (pin "9") (pinfunction "9_9") (pintype "bidirectional"))
      (node (ref "J9") (pin "1") (pinfunction "1_1") (pintype "bidirectional"))
      (node (ref "J9") (pin "5") (pinfunction "5_5") (pintype "bidirectional"))
      (node (ref "J9") (pin "9") (pinfunction "9_9") (pintype "bidirectional"))
      (node (ref "J9R") (pin "2") (pinfunction "2_2") (pintype "bidirectional"))
      (node (ref "J9R") (pin "9") (pinfunction "9_9") (pintype "bidirectional"))
      (node (ref "LD1") (pin "1") (pinfunction "C_1") (pintype "passive"))
      (node (ref "MP1") (pin "1") (pinfunction "1_1") (pintype "passive"))
      (node (ref "MP2") (pin "1") (pinfunction "1_1") (pintype "passive"))
      (node (ref "MP3") (pin "1") (pinfunction "1_1") (pintype "passive"))
      (node (ref "MP4") (pin "1") (pinfunction "1_1") (pintype "passive"))
      (node (ref "NT1") (pin "2") (pinfunction "2_2") (pintype "bidirectional"))
      (node (ref "NT10") (pin "2") (pinfunction "2_2") (pintype "bidirectional"))
      (node (ref "NT11") (pin "2") (pinfunction "2_2") (pintype "bidirectional"))
      (node (ref "NT12") (pin "2") (pinfunction "2_2") (pintype "bidirectional"))
      (node (ref "NT2") (pin "2") (pinfunction "2_2") (pintype "bidirectional"))
      (node (ref "NT3") (pin "2") (pinfunction "2_2") (pintype "bidirectional"))
      (node (ref "NT4") (pin "2") (pinfunction "2_2") (pintype "bidirectional"))
      (node (ref "NT5") (pin "2") (pinfunction "2_2") (pintype "bidirectional"))
      (node (ref "NT6") (pin "2") (pinfunction "2_2") (pintype "bidirectional"))
      (node (ref "NT7") (pin "2") (pinfunction "2_2") (pintype "bidirectional"))
      (node (ref "NT8") (pin "2") (pinfunction "2_2") (pintype "bidirectional"))
      (node (ref "NT9") (pin "2") (pinfunction "2_2") (pintype "bidirectional"))
      (node (ref "SW2") (pin "5") (pinfunction "5_5") (pintype "bidirectional"))
      (node (ref "SW2") (pin "6") (pinfunction "6_6") (pintype "bidirectional"))
      (node (ref "SW2") (pin "7") (pinfunction "7_7") (pintype "bidirectional"))
      (node (ref "SW2") (pin "8") (pinfunction "8_8") (pintype "bidirectional"))
    )
    (net (code "63") (name "Net-(LD1-A)") (class "Default")
      (node (ref "LD1") (pin "2") (pinfunction "A_2") (pintype "passive"))
      (node (ref "R34") (pin "1") (pinfunction "1_1") (pintype "passive"))
    )
    (net (code "64") (name "Net-(LD18-C)") (class "Default")
      (node (ref "LD18") (pin "1") (pinfunction "C_1") (pintype "passive"))
      (node (ref "R26") (pin "1") (pinfunction "1_1") (pintype "passive"))
    )
    (net (code "65") (name "Net-(LD19-C)") (class "Default")
      (node (ref "LD19") (pin "1") (pinfunction "C_1") (pintype "passive"))
      (node (ref "R27") (pin "1") (pinfunction "1_1") (pintype "passive"))
    )
    (net (code "66") (name "Net-(LD20-C)") (class "Default")
      (node (ref "LD20") (pin "1") (pinfunction "C_1") (pintype "passive"))
      (node (ref "R32") (pin "1") (pinfunction "1_1") (pintype "passive"))
    )
    (net (code "67") (name "Net-(LD21-C)") (class "Default")
      (node (ref "LD21") (pin "1") (pinfunction "C_1") (pintype "passive"))
      (node (ref "R33") (pin "1") (pinfunction "1_1") (pintype "passive"))
    )
    (net (code "68") (name "P1V8") (class "Default")
      (node (ref "C21") (pin "2") (pinfunction "2_2") (pintype "passive"))
      (node (ref "C232") (pin "2") (pinfunction "2_2") (pintype "passive"))
      (node (ref "C61") (pin "2") (pinfunction "2_2") (pintype "passive"))
      (node (ref "IC3") (pin "41") (pinfunction "VCCINT_41") (pintype "power_in"))
      (node (ref "IC3") (pin "8") (pinfunction "VCCINT_8") (pintype "power_in"))
      (node (ref "IC4") (pin "5") (pinfunction "VOUT_5") (pintype "power_in"))
    )
    (net (code "69") (name "P3V3") (class "Default")
      (node (ref "C11") (pin "2") (pinfunction "2_2") (pintype "passive"))
      (node (ref "C19") (pin "2") (pinfunction "2_2") (pintype "passive"))
      (node (ref "C2") (pin "2") (pinfunction "2_2") (pintype "passive"))
      (node (ref "C3") (pin "2") (pinfunction "2_2") (pintype "passive"))
      (node (ref "C4") (pin "2") (pinfunction "2_2") (pintype "passive"))
      (node (ref "D5") (pin "1") (pinfunction "C_1") (pintype "passive"))
      (node (ref "IC3") (pin "23") (pinfunction "VCCIO1_23") (pintype "power_in"))
      (node (ref "IC3") (pin "39") (pinfunction "VCCIO2_39") (pintype "power_in"))
      (node (ref "IC3") (pin "57") (pinfunction "VCCIO2_57") (pintype "power_in"))
      (node (ref "IC3") (pin "6") (pinfunction "VCCIO1_6") (pintype "power_in"))
      (node (ref "IC7") (pin "5") (pinfunction "VOUT_5") (pintype "power_in"))
      (node (ref "J13") (pin "4") (pinfunction "4_4") (pintype "bidirectional"))
      (node (ref "LD18") (pin "2") (pinfunction "A_2") (pintype "passive"))
      (node (ref "LD19") (pin "2") (pinfunction "A_2") (pintype "passive"))
      (node (ref "LD20") (pin "2") (pinfunction "A_2") (pintype "passive"))
      (node (ref "LD21") (pin "2") (pinfunction "A_2") (pintype "passive"))
    )
    (net (code "70") (name "P5V0") (class "Default")
      (node (ref "C20") (pin "2") (pinfunction "2_2") (pintype "passive"))
      (node (ref "C231") (pin "2") (pinfunction "2_2") (pintype "passive"))
      (node (ref "IC4") (pin "1") (pinfunction "VIN_1") (pintype "input"))
      (node (ref "IC4") (pin "3") (pinfunction "EN_3") (pintype "input"))
      (node (ref "IC7") (pin "1") (pinfunction "VIN_1") (pintype "input"))
      (node (ref "IC7") (pin "3") (pinfunction "EN_3") (pintype "input"))
      (node (ref "J10") (pin "2") (pinfunction "2_2") (pintype "bidirectional"))
      (node (ref "J100") (pin "1") (pinfunction "1_1") (pintype "bidirectional"))
      (node (ref "J11") (pin "2") (pinfunction "2_2") (pintype "bidirectional"))
      (node (ref "J12") (pin "1") (pinfunction "1_1") (pintype "bidirectional"))
    )
    (net (code "71") (name "P12V0") (class "Default")
      (node (ref "J10") (pin "1") (pinfunction "1_1") (pintype "bidirectional"))
      (node (ref "J10") (pin "3") (pinfunction "3_3") (pintype "bidirectional"))
      (node (ref "J100") (pin "2") (pinfunction "2_2") (pintype "bidirectional"))
      (node (ref "J11") (pin "1") (pinfunction "1_1") (pintype "bidirectional"))
      (node (ref "J11") (pin "3") (pinfunction "3_3") (pintype "bidirectional"))
      (node (ref "J12") (pin "2") (pinfunction "2_2") (pintype "bidirectional"))
    )
    (net (code "72") (name "unconnected-(IC4-NC-Pad4)") (class "Default")
      (node (ref "IC4") (pin "4") (pinfunction "NC_4") (pintype "passive"))
    )
    (net (code "73") (name "unconnected-(IC7-NC-Pad4)") (class "Default")
      (node (ref "IC7") (pin "4") (pinfunction "NC_4") (pintype "passive"))
    )
    (net (code "74") (name "unconnected-(J13-Pad6)") (class "Default")
      (node (ref "J13") (pin "6") (pinfunction "6_6") (pintype "bidirectional"))
    )
    (net (code "75") (name "unconnected-(J13-Pad7)") (class "Default")
      (node (ref "J13") (pin "7") (pinfunction "7_7") (pintype "bidirectional"))
    )
    (net (code "76") (name "unconnected-(J13-Pad8)") (class "Default")
      (node (ref "J13") (pin "8") (pinfunction "8_8") (pintype "bidirectional"))
    )
  )
)
